# buck_converters_v1_1.net
KiCad netlist of a schematic drawn in EAGLE
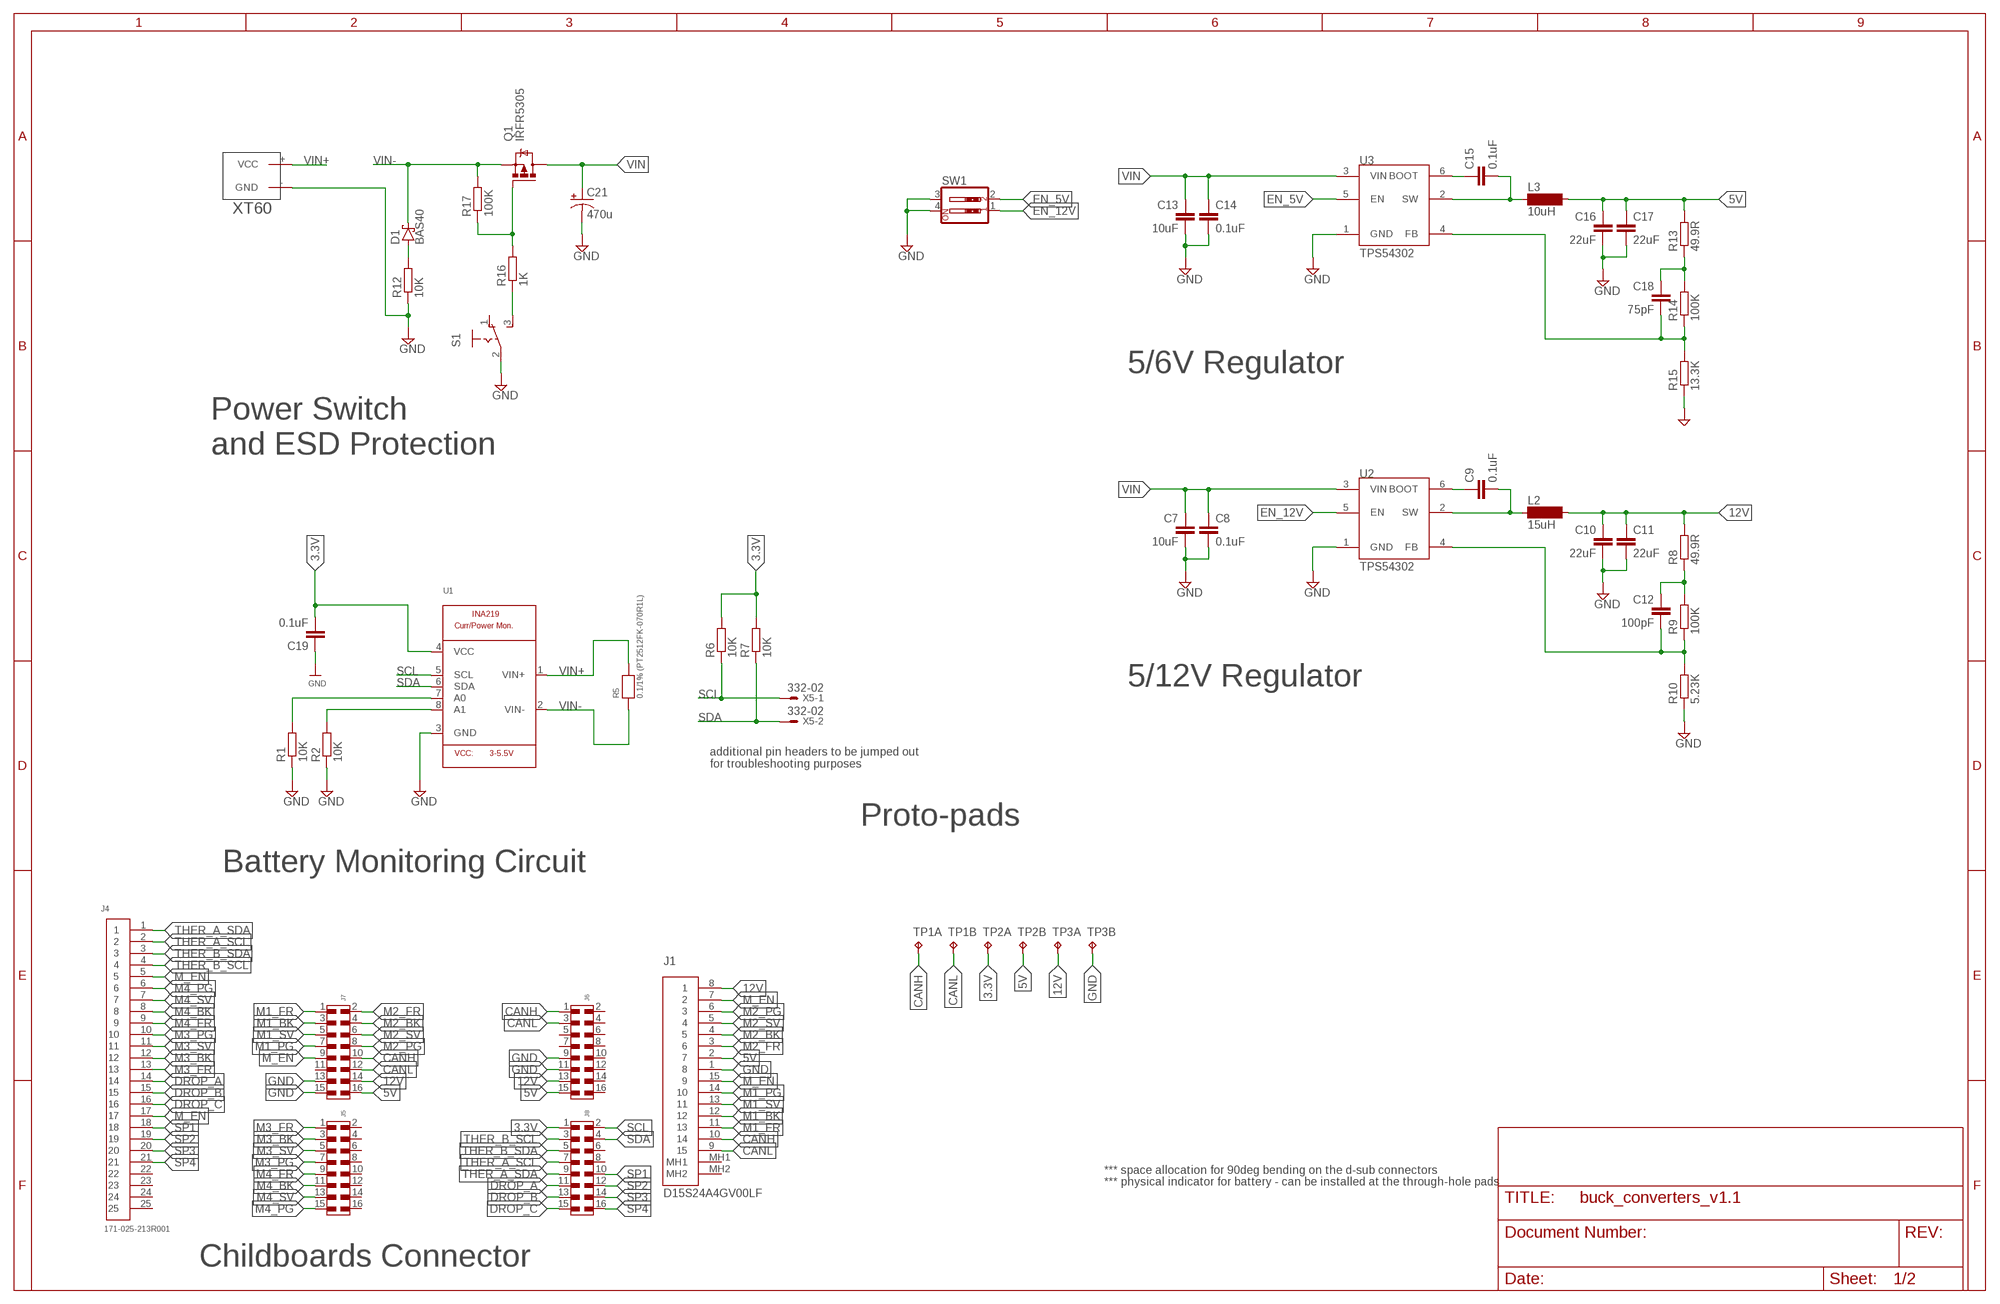
[diagram p0: schematic, sheet 1]
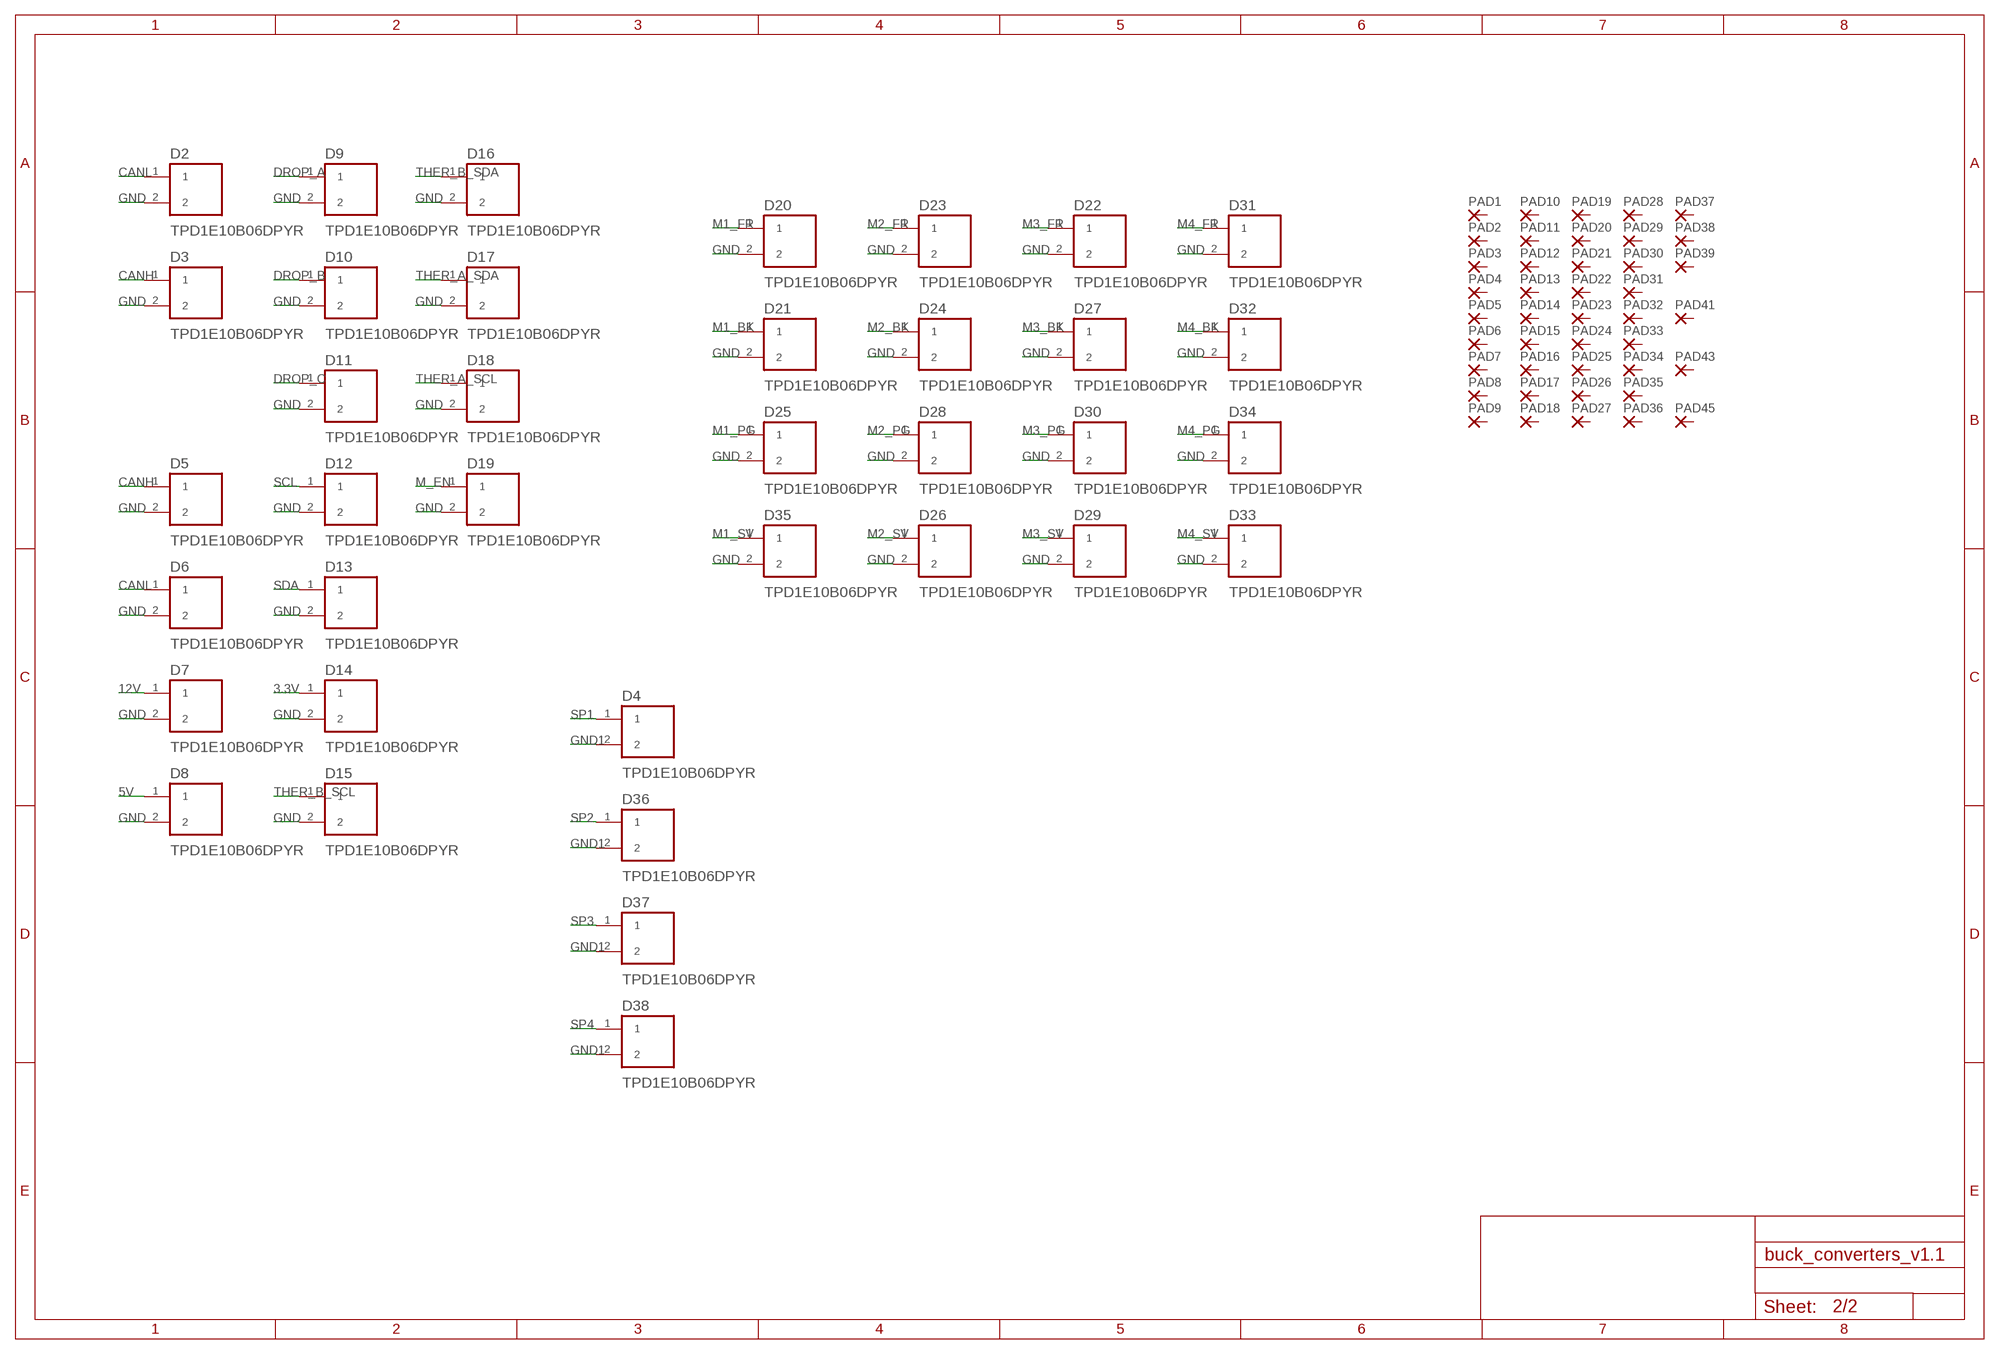
[diagram p1: schematic, sheet 2]

(export (version "E")
  (design (tool "Eeschema 10.0.6"))
  (components
    (comp (ref "D2")
      (value "TPD1E10B06DPYR")
      (footprint "eagle-import:DIO_TPD1E05U06DPYR")
      (fields (field (name "MF") "Texas Instruments"))
      (libsource (lib "eagle-import") (part "TPD1E10B06DPYR"))
    )
    (comp (ref "D3")
      (value "TPD1E10B06DPYR")
      (footprint "eagle-import:DIO_TPD1E05U06DPYR")
      (fields (field (name "MF") "Texas Instruments"))
      (libsource (lib "eagle-import") (part "TPD1E10B06DPYR"))
    )
    (comp (ref "D4")
      (value "TPD1E10B06DPYR")
      (footprint "eagle-import:DIO_TPD1E05U06DPYR")
      (fields (field (name "MF") "Texas Instruments"))
      (libsource (lib "eagle-import") (part "TPD1E10B06DPYR"))
    )
    (comp (ref "D5")
      (value "TPD1E10B06DPYR")
      (footprint "eagle-import:DIO_TPD1E05U06DPYR")
      (fields (field (name "MF") "Texas Instruments"))
      (libsource (lib "eagle-import") (part "TPD1E10B06DPYR"))
    )
    (comp (ref "D6")
      (value "TPD1E10B06DPYR")
      (footprint "eagle-import:DIO_TPD1E05U06DPYR")
      (fields (field (name "MF") "Texas Instruments"))
      (libsource (lib "eagle-import") (part "TPD1E10B06DPYR"))
    )
    (comp (ref "D7")
      (value "TPD1E10B06DPYR")
      (footprint "eagle-import:DIO_TPD1E05U06DPYR")
      (fields (field (name "MF") "Texas Instruments"))
      (libsource (lib "eagle-import") (part "TPD1E10B06DPYR"))
    )
    (comp (ref "D8")
      (value "TPD1E10B06DPYR")
      (footprint "eagle-import:DIO_TPD1E05U06DPYR")
      (fields (field (name "MF") "Texas Instruments"))
      (libsource (lib "eagle-import") (part "TPD1E10B06DPYR"))
    )
    (comp (ref "D9")
      (value "TPD1E10B06DPYR")
      (footprint "eagle-import:DIO_TPD1E05U06DPYR")
      (fields (field (name "MF") "Texas Instruments"))
      (libsource (lib "eagle-import") (part "TPD1E10B06DPYR"))
    )
    (comp (ref "D10")
      (value "TPD1E10B06DPYR")
      (footprint "eagle-import:DIO_TPD1E05U06DPYR")
      (fields (field (name "MF") "Texas Instruments"))
      (libsource (lib "eagle-import") (part "TPD1E10B06DPYR"))
    )
    (comp (ref "D11")
      (value "TPD1E10B06DPYR")
      (footprint "eagle-import:DIO_TPD1E05U06DPYR")
      (fields (field (name "MF") "Texas Instruments"))
      (libsource (lib "eagle-import") (part "TPD1E10B06DPYR"))
    )
    (comp (ref "D12")
      (value "TPD1E10B06DPYR")
      (footprint "eagle-import:DIO_TPD1E05U06DPYR")
      (fields (field (name "MF") "Texas Instruments"))
      (libsource (lib "eagle-import") (part "TPD1E10B06DPYR"))
    )
    (comp (ref "D13")
      (value "TPD1E10B06DPYR")
      (footprint "eagle-import:DIO_TPD1E05U06DPYR")
      (fields (field (name "MF") "Texas Instruments"))
      (libsource (lib "eagle-import") (part "TPD1E10B06DPYR"))
    )
    (comp (ref "D14")
      (value "TPD1E10B06DPYR")
      (footprint "eagle-import:DIO_TPD1E05U06DPYR")
      (fields (field (name "MF") "Texas Instruments"))
      (libsource (lib "eagle-import") (part "TPD1E10B06DPYR"))
    )
    (comp (ref "D15")
      (value "TPD1E10B06DPYR")
      (footprint "eagle-import:DIO_TPD1E05U06DPYR")
      (fields (field (name "MF") "Texas Instruments"))
      (libsource (lib "eagle-import") (part "TPD1E10B06DPYR"))
    )
    (comp (ref "D16")
      (value "TPD1E10B06DPYR")
      (footprint "eagle-import:DIO_TPD1E05U06DPYR")
      (fields (field (name "MF") "Texas Instruments"))
      (libsource (lib "eagle-import") (part "TPD1E10B06DPYR"))
    )
    (comp (ref "D17")
      (value "TPD1E10B06DPYR")
      (footprint "eagle-import:DIO_TPD1E05U06DPYR")
      (fields (field (name "MF") "Texas Instruments"))
      (libsource (lib "eagle-import") (part "TPD1E10B06DPYR"))
    )
    (comp (ref "D18")
      (value "TPD1E10B06DPYR")
      (footprint "eagle-import:DIO_TPD1E05U06DPYR")
      (fields (field (name "MF") "Texas Instruments"))
      (libsource (lib "eagle-import") (part "TPD1E10B06DPYR"))
    )
    (comp (ref "D19")
      (value "TPD1E10B06DPYR")
      (footprint "eagle-import:DIO_TPD1E05U06DPYR")
      (fields (field (name "MF") "Texas Instruments"))
      (libsource (lib "eagle-import") (part "TPD1E10B06DPYR"))
    )
    (comp (ref "D20")
      (value "TPD1E10B06DPYR")
      (footprint "eagle-import:DIO_TPD1E05U06DPYR")
      (fields (field (name "MF") "Texas Instruments"))
      (libsource (lib "eagle-import") (part "TPD1E10B06DPYR"))
    )
    (comp (ref "D21")
      (value "TPD1E10B06DPYR")
      (footprint "eagle-import:DIO_TPD1E05U06DPYR")
      (fields (field (name "MF") "Texas Instruments"))
      (libsource (lib "eagle-import") (part "TPD1E10B06DPYR"))
    )
    (comp (ref "D22")
      (value "TPD1E10B06DPYR")
      (footprint "eagle-import:DIO_TPD1E05U06DPYR")
      (fields (field (name "MF") "Texas Instruments"))
      (libsource (lib "eagle-import") (part "TPD1E10B06DPYR"))
    )
    (comp (ref "D23")
      (value "TPD1E10B06DPYR")
      (footprint "eagle-import:DIO_TPD1E05U06DPYR")
      (fields (field (name "MF") "Texas Instruments"))
      (libsource (lib "eagle-import") (part "TPD1E10B06DPYR"))
    )
    (comp (ref "D24")
      (value "TPD1E10B06DPYR")
      (footprint "eagle-import:DIO_TPD1E05U06DPYR")
      (fields (field (name "MF") "Texas Instruments"))
      (libsource (lib "eagle-import") (part "TPD1E10B06DPYR"))
    )
    (comp (ref "D25")
      (value "TPD1E10B06DPYR")
      (footprint "eagle-import:DIO_TPD1E05U06DPYR")
      (fields (field (name "MF") "Texas Instruments"))
      (libsource (lib "eagle-import") (part "TPD1E10B06DPYR"))
    )
    (comp (ref "D26")
      (value "TPD1E10B06DPYR")
      (footprint "eagle-import:DIO_TPD1E05U06DPYR")
      (fields (field (name "MF") "Texas Instruments"))
      (libsource (lib "eagle-import") (part "TPD1E10B06DPYR"))
    )
    (comp (ref "D27")
      (value "TPD1E10B06DPYR")
      (footprint "eagle-import:DIO_TPD1E05U06DPYR")
      (fields (field (name "MF") "Texas Instruments"))
      (libsource (lib "eagle-import") (part "TPD1E10B06DPYR"))
    )
    (comp (ref "D28")
      (value "TPD1E10B06DPYR")
      (footprint "eagle-import:DIO_TPD1E05U06DPYR")
      (fields (field (name "MF") "Texas Instruments"))
      (libsource (lib "eagle-import") (part "TPD1E10B06DPYR"))
    )
    (comp (ref "D29")
      (value "TPD1E10B06DPYR")
      (footprint "eagle-import:DIO_TPD1E05U06DPYR")
      (fields (field (name "MF") "Texas Instruments"))
      (libsource (lib "eagle-import") (part "TPD1E10B06DPYR"))
    )
    (comp (ref "D30")
      (value "TPD1E10B06DPYR")
      (footprint "eagle-import:DIO_TPD1E05U06DPYR")
      (fields (field (name "MF") "Texas Instruments"))
      (libsource (lib "eagle-import") (part "TPD1E10B06DPYR"))
    )
    (comp (ref "D31")
      (value "TPD1E10B06DPYR")
      (footprint "eagle-import:DIO_TPD1E05U06DPYR")
      (fields (field (name "MF") "Texas Instruments"))
      (libsource (lib "eagle-import") (part "TPD1E10B06DPYR"))
    )
    (comp (ref "D32")
      (value "TPD1E10B06DPYR")
      (footprint "eagle-import:DIO_TPD1E05U06DPYR")
      (fields (field (name "MF") "Texas Instruments"))
      (libsource (lib "eagle-import") (part "TPD1E10B06DPYR"))
    )
    (comp (ref "D33")
      (value "TPD1E10B06DPYR")
      (footprint "eagle-import:DIO_TPD1E05U06DPYR")
      (fields (field (name "MF") "Texas Instruments"))
      (libsource (lib "eagle-import") (part "TPD1E10B06DPYR"))
    )
    (comp (ref "D34")
      (value "TPD1E10B06DPYR")
      (footprint "eagle-import:DIO_TPD1E05U06DPYR")
      (fields (field (name "MF") "Texas Instruments"))
      (libsource (lib "eagle-import") (part "TPD1E10B06DPYR"))
    )
    (comp (ref "D35")
      (value "TPD1E10B06DPYR")
      (footprint "eagle-import:DIO_TPD1E05U06DPYR")
      (fields (field (name "MF") "Texas Instruments"))
      (libsource (lib "eagle-import") (part "TPD1E10B06DPYR"))
    )
    (comp (ref "D36")
      (value "TPD1E10B06DPYR")
      (footprint "eagle-import:DIO_TPD1E05U06DPYR")
      (fields (field (name "MF") "Texas Instruments"))
      (libsource (lib "eagle-import") (part "TPD1E10B06DPYR"))
    )
    (comp (ref "D37")
      (value "TPD1E10B06DPYR")
      (footprint "eagle-import:DIO_TPD1E05U06DPYR")
      (fields (field (name "MF") "Texas Instruments"))
      (libsource (lib "eagle-import") (part "TPD1E10B06DPYR"))
    )
    (comp (ref "D38")
      (value "TPD1E10B06DPYR")
      (footprint "eagle-import:DIO_TPD1E05U06DPYR")
      (fields (field (name "MF") "Texas Instruments"))
      (libsource (lib "eagle-import") (part "TPD1E10B06DPYR"))
    )
    (comp (ref "PAD1")
      (value "2,54/1,1")
      (footprint "eagle-import:2,54_1,1")
      (libsource (lib "eagle-import") (part "2,54/1,1"))
    )
    (comp (ref "PAD2")
      (value "2,54/1,1")
      (footprint "eagle-import:2,54_1,1")
      (libsource (lib "eagle-import") (part "2,54/1,1"))
    )
    (comp (ref "PAD3")
      (value "2,54/1,1")
      (footprint "eagle-import:2,54_1,1")
      (libsource (lib "eagle-import") (part "2,54/1,1"))
    )
    (comp (ref "PAD4")
      (value "2,54/1,1")
      (footprint "eagle-import:2,54_1,1")
      (libsource (lib "eagle-import") (part "2,54/1,1"))
    )
    (comp (ref "PAD5")
      (value "2,54/1,1")
      (footprint "eagle-import:2,54_1,1")
      (libsource (lib "eagle-import") (part "2,54/1,1"))
    )
    (comp (ref "PAD6")
      (value "2,54/1,1")
      (footprint "eagle-import:2,54_1,1")
      (libsource (lib "eagle-import") (part "2,54/1,1"))
    )
    (comp (ref "PAD7")
      (value "2,54/1,1")
      (footprint "eagle-import:2,54_1,1")
      (libsource (lib "eagle-import") (part "2,54/1,1"))
    )
    (comp (ref "PAD8")
      (value "2,54/1,1")
      (footprint "eagle-import:2,54_1,1")
      (libsource (lib "eagle-import") (part "2,54/1,1"))
    )
    (comp (ref "PAD9")
      (value "2,54/1,1")
      (footprint "eagle-import:2,54_1,1")
      (libsource (lib "eagle-import") (part "2,54/1,1"))
    )
    (comp (ref "PAD10")
      (value "2,54/1,1")
      (footprint "eagle-import:2,54_1,1")
      (libsource (lib "eagle-import") (part "2,54/1,1"))
    )
    (comp (ref "PAD11")
      (value "2,54/1,1")
      (footprint "eagle-import:2,54_1,1")
      (libsource (lib "eagle-import") (part "2,54/1,1"))
    )
    (comp (ref "PAD12")
      (value "2,54/1,1")
      (footprint "eagle-import:2,54_1,1")
      (libsource (lib "eagle-import") (part "2,54/1,1"))
    )
    (comp (ref "PAD13")
      (value "2,54/1,1")
      (footprint "eagle-import:2,54_1,1")
      (libsource (lib "eagle-import") (part "2,54/1,1"))
    )
    (comp (ref "PAD14")
      (value "2,54/1,1")
      (footprint "eagle-import:2,54_1,1")
      (libsource (lib "eagle-import") (part "2,54/1,1"))
    )
    (comp (ref "PAD15")
      (value "2,54/1,1")
      (footprint "eagle-import:2,54_1,1")
      (libsource (lib "eagle-import") (part "2,54/1,1"))
    )
    (comp (ref "PAD16")
      (value "2,54/1,1")
      (footprint "eagle-import:2,54_1,1")
      (libsource (lib "eagle-import") (part "2,54/1,1"))
    )
    (comp (ref "PAD17")
      (value "2,54/1,1")
      (footprint "eagle-import:2,54_1,1")
      (libsource (lib "eagle-import") (part "2,54/1,1"))
    )
    (comp (ref "PAD18")
      (value "2,54/1,1")
      (footprint "eagle-import:2,54_1,1")
      (libsource (lib "eagle-import") (part "2,54/1,1"))
    )
    (comp (ref "PAD19")
      (value "2,54/1,1")
      (footprint "eagle-import:2,54_1,1")
      (libsource (lib "eagle-import") (part "2,54/1,1"))
    )
    (comp (ref "PAD20")
      (value "2,54/1,1")
      (footprint "eagle-import:2,54_1,1")
      (libsource (lib "eagle-import") (part "2,54/1,1"))
    )
    (comp (ref "PAD21")
      (value "2,54/1,1")
      (footprint "eagle-import:2,54_1,1")
      (libsource (lib "eagle-import") (part "2,54/1,1"))
    )
    (comp (ref "PAD22")
      (value "2,54/1,1")
      (footprint "eagle-import:2,54_1,1")
      (libsource (lib "eagle-import") (part "2,54/1,1"))
    )
    (comp (ref "PAD23")
      (value "2,54/1,1")
      (footprint "eagle-import:2,54_1,1")
      (libsource (lib "eagle-import") (part "2,54/1,1"))
    )
    (comp (ref "PAD24")
      (value "2,54/1,1")
      (footprint "eagle-import:2,54_1,1")
      (libsource (lib "eagle-import") (part "2,54/1,1"))
    )
    (comp (ref "PAD25")
      (value "2,54/1,1")
      (footprint "eagle-import:2,54_1,1")
      (libsource (lib "eagle-import") (part "2,54/1,1"))
    )
    (comp (ref "PAD26")
      (value "2,54/1,1")
      (footprint "eagle-import:2,54_1,1")
      (libsource (lib "eagle-import") (part "2,54/1,1"))
    )
    (comp (ref "PAD27")
      (value "2,54/1,1")
      (footprint "eagle-import:2,54_1,1")
      (libsource (lib "eagle-import") (part "2,54/1,1"))
    )
    (comp (ref "PAD28")
      (value "2,54/1,1")
      (footprint "eagle-import:2,54_1,1")
      (libsource (lib "eagle-import") (part "2,54/1,1"))
    )
    (comp (ref "PAD29")
      (value "2,54/1,1")
      (footprint "eagle-import:2,54_1,1")
      (libsource (lib "eagle-import") (part "2,54/1,1"))
    )
    (comp (ref "PAD30")
      (value "2,54/1,1")
      (footprint "eagle-import:2,54_1,1")
      (libsource (lib "eagle-import") (part "2,54/1,1"))
    )
    (comp (ref "PAD31")
      (value "2,54/1,1")
      (footprint "eagle-import:2,54_1,1")
      (libsource (lib "eagle-import") (part "2,54/1,1"))
    )
    (comp (ref "PAD32")
      (value "2,54/1,1")
      (footprint "eagle-import:2,54_1,1")
      (libsource (lib "eagle-import") (part "2,54/1,1"))
    )
    (comp (ref "PAD33")
      (value "2,54/1,1")
      (footprint "eagle-import:2,54_1,1")
      (libsource (lib "eagle-import") (part "2,54/1,1"))
    )
    (comp (ref "PAD34")
      (value "2,54/1,1")
      (footprint "eagle-import:2,54_1,1")
      (libsource (lib "eagle-import") (part "2,54/1,1"))
    )
    (comp (ref "PAD35")
      (value "2,54/1,1")
      (footprint "eagle-import:2,54_1,1")
      (libsource (lib "eagle-import") (part "2,54/1,1"))
    )
    (comp (ref "PAD36")
      (value "2,54/1,1")
      (footprint "eagle-import:2,54_1,1")
      (libsource (lib "eagle-import") (part "2,54/1,1"))
    )
    (comp (ref "PAD37")
      (value "2,54/1,1")
      (footprint "eagle-import:2,54_1,1")
      (libsource (lib "eagle-import") (part "2,54/1,1"))
    )
    (comp (ref "PAD38")
      (value "2,54/1,1")
      (footprint "eagle-import:2,54_1,1")
      (libsource (lib "eagle-import") (part "2,54/1,1"))
    )
    (comp (ref "PAD39")
      (value "2,54/1,1")
      (footprint "eagle-import:2,54_1,1")
      (libsource (lib "eagle-import") (part "2,54/1,1"))
    )
    (comp (ref "PAD41")
      (value "2,54/1,1")
      (footprint "eagle-import:2,54_1,1")
      (libsource (lib "eagle-import") (part "2,54/1,1"))
    )
    (comp (ref "PAD43")
      (value "2,54/1,1")
      (footprint "eagle-import:2,54_1,1")
      (libsource (lib "eagle-import") (part "2,54/1,1"))
    )
    (comp (ref "PAD45")
      (value "2,54/1,1")
      (footprint "eagle-import:2,54_1,1")
      (libsource (lib "eagle-import") (part "2,54/1,1"))
    )
    (comp (ref "C7")
      (value "10uF")
      (footprint "eagle-import:C0805")
      (libsource (lib "eagle-import") (part "C-EUC0805"))
    )
    (comp (ref "C8")
      (value "0.1uF")
      (footprint "eagle-import:C0805")
      (libsource (lib "eagle-import") (part "C-EUC0805"))
    )
    (comp (ref "C9")
      (value "0.1uF")
      (footprint "eagle-import:C0805")
      (libsource (lib "eagle-import") (part "C-EUC0805"))
    )
    (comp (ref "C10")
      (value "22uF")
      (footprint "eagle-import:C0805")
      (libsource (lib "eagle-import") (part "C-EUC0805"))
    )
    (comp (ref "C11")
      (value "22uF")
      (footprint "eagle-import:C0805")
      (libsource (lib "eagle-import") (part "C-EUC0805"))
    )
    (comp (ref "C12")
      (value "100pF")
      (footprint "eagle-import:C0805")
      (libsource (lib "eagle-import") (part "C-EUC0805"))
    )
    (comp (ref "C13")
      (value "10uF")
      (footprint "eagle-import:C0805")
      (libsource (lib "eagle-import") (part "C-EUC0805"))
    )
    (comp (ref "C14")
      (value "0.1uF")
      (footprint "eagle-import:C0805")
      (libsource (lib "eagle-import") (part "C-EUC0805"))
    )
    (comp (ref "C15")
      (value "0.1uF")
      (footprint "eagle-import:C0805")
      (libsource (lib "eagle-import") (part "C-EUC0805"))
    )
    (comp (ref "C16")
      (value "22uF")
      (footprint "eagle-import:C0805")
      (libsource (lib "eagle-import") (part "C-EUC0805"))
    )
    (comp (ref "C17")
      (value "22uF")
      (footprint "eagle-import:C0805")
      (libsource (lib "eagle-import") (part "C-EUC0805"))
    )
    (comp (ref "C18")
      (value "75pF")
      (footprint "eagle-import:C0805")
      (libsource (lib "eagle-import") (part "C-EUC0805"))
    )
    (comp (ref "C19")
      (value "0.1uF")
      (footprint "eagle-import:C0805")
      (libsource (lib "eagle-import") (part "C-EUC0805"))
    )
    (comp (ref "C21")
      (value "470u")
      (footprint "eagle-import:153CLV-1010")
      (libsource (lib "eagle-import") (part "CPOL-US153CLV-1010"))
    )
    (comp (ref "D1")
      (value "BAS40")
      (footprint "eagle-import:SOT23")
      (libsource (lib "eagle-import") (part "BAS40"))
    )
    (comp (ref "J1")
      (value "D15S24A4GV00LF")
      (footprint "eagle-import:D15S24A4GV00LF")
      (fields
        (field (name "DIGIKEY_PART_NUMBER") "609-1497-ND")
        (field (name "MANUFACTURER") "Amphenol ICC (FCI)")
        (field (name "CREATED_BY") "PCBLayout.com")
      )
      (libsource (lib "eagle-import") (part "D15S24A4GV00LF"))
    )
    (comp (ref "J4")
      (value "171-025-213R001")
      (footprint "eagle-import:171-025-213R001")
      (fields
        (field (name "DIGIKEY_PART_NO") "4225FE-ND")
        (field (name "MANUFACTURER") "NorComp Inc.")
        (field (name "CREATED_BY") "PCBLayout.com")
      )
      (libsource (lib "eagle-import") (part "171-025-213R001"))
    )
    (comp (ref "J5")
      (value "6120XX20621_61201620621")
      (footprint "eagle-import:61201620621")
      (libsource (lib "eagle-import") (part "6120XX20621_61201620621"))
    )
    (comp (ref "J6")
      (value "6120XX20621_61201620621")
      (footprint "eagle-import:61201620621")
      (libsource (lib "eagle-import") (part "6120XX20621_61201620621"))
    )
    (comp (ref "J7")
      (value "6123XX20621_61231620621")
      (footprint "eagle-import:61231620621")
      (libsource (lib "eagle-import") (part "6123XX20621_61231620621"))
    )
    (comp (ref "J8")
      (value "6120XX20621_61201620621")
      (footprint "eagle-import:61201620621")
      (libsource (lib "eagle-import") (part "6120XX20621_61201620621"))
    )
    (comp (ref "L2")
      (value "15uH")
      (footprint "eagle-import:SM-NE29")
      (libsource (lib "eagle-import") (part "SM-NE29"))
    )
    (comp (ref "L3")
      (value "10uH")
      (footprint "eagle-import:SM-NE29")
      (libsource (lib "eagle-import") (part "SM-NE29"))
    )
    (comp (ref "Q1")
      (value "IRFR5305")
      (footprint "eagle-import:D-PAK_TO252AA")
      (libsource (lib "eagle-import") (part "IRF?5305R"))
    )
    (comp (ref "R1")
      (value "10K")
      (footprint "eagle-import:R0805")
      (libsource (lib "eagle-import") (part "R-EU_R0805"))
    )
    (comp (ref "R2")
      (value "10K")
      (footprint "eagle-import:R0805")
      (libsource (lib "eagle-import") (part "R-EU_R0805"))
    )
    (comp (ref "R5")
      (value "0.1/1% (PT2512FK-070R1L)")
      (footprint "eagle-import:2512")
      (libsource (lib "eagle-import") (part "RESISTOR2512"))
    )
    (comp (ref "R6")
      (value "10K")
      (footprint "eagle-import:R0805")
      (libsource (lib "eagle-import") (part "R-EU_R0805"))
    )
    (comp (ref "R7")
      (value "10K")
      (footprint "eagle-import:R0805")
      (libsource (lib "eagle-import") (part "R-EU_R0805"))
    )
    (comp (ref "R8")
      (value "49.9R")
      (footprint "eagle-import:R0805")
      (libsource (lib "eagle-import") (part "R-EU_R0805"))
    )
    (comp (ref "R9")
      (value "100K")
      (footprint "eagle-import:R0805")
      (libsource (lib "eagle-import") (part "R-EU_R0805"))
    )
    (comp (ref "R10")
      (value "5.23K")
      (footprint "eagle-import:R0805")
      (libsource (lib "eagle-import") (part "R-EU_R0805"))
    )
    (comp (ref "R12")
      (value "10K")
      (footprint "eagle-import:R0805")
      (libsource (lib "eagle-import") (part "R-EU_R0805"))
    )
    (comp (ref "R13")
      (value "49.9R")
      (footprint "eagle-import:R0805")
      (libsource (lib "eagle-import") (part "R-EU_R0805"))
    )
    (comp (ref "R14")
      (value "100K")
      (footprint "eagle-import:R0805")
      (libsource (lib "eagle-import") (part "R-EU_R0805"))
    )
    (comp (ref "R15")
      (value "13.3K")
      (footprint "eagle-import:R0805")
      (libsource (lib "eagle-import") (part "R-EU_R0805"))
    )
    (comp (ref "R16")
      (value "1K")
      (footprint "eagle-import:R0805")
      (libsource (lib "eagle-import") (part "R-EU_R0805"))
    )
    (comp (ref "R17")
      (value "100K")
      (footprint "eagle-import:R0805")
      (libsource (lib "eagle-import") (part "R-EU_R0805"))
    )
    (comp (ref "S1")
      (value "255SB")
      (footprint "eagle-import:255SB")
      (libsource (lib "eagle-import") (part "255SB"))
    )
    (comp (ref "SW1")
      (value "SW_DIP-2")
      (footprint "eagle-import:EDG-02")
      (libsource (lib "eagle-import") (part "SW_DIP-2"))
    )
    (comp (ref "TP1")
      (value "TP2P2-38-17")
      (footprint "eagle-import:P2-38-17")
      (libsource (lib "eagle-import") (part "TP2P2-38-17"))
    )
    (comp (ref "TP2")
      (value "TP2P2-38-17")
      (footprint "eagle-import:P2-38-17")
      (libsource (lib "eagle-import") (part "TP2P2-38-17"))
    )
    (comp (ref "TP3")
      (value "TP2P2-38-17")
      (footprint "eagle-import:P2-38-17")
      (libsource (lib "eagle-import") (part "TP2P2-38-17"))
    )
    (comp (ref "U$9")
      (value "XT60")
      (footprint "eagle-import:XT60")
      (libsource (lib "eagle-import") (part "XT60"))
    )
    (comp (ref "U1")
      (value "INA219")
      (footprint "eagle-import:SOT23-8")
      (libsource (lib "eagle-import") (part "INA219"))
    )
    (comp (ref "U2")
      (value "TPS54302")
      (footprint "eagle-import:SOT23-6")
      (libsource (lib "eagle-import") (part "TPS54302"))
    )
    (comp (ref "U3")
      (value "TPS54302")
      (footprint "eagle-import:SOT23-6")
      (libsource (lib "eagle-import") (part "TPS54302"))
    )
    (comp (ref "X5")
      (value "332-02")
      (footprint "eagle-import:332-02")
      (libsource (lib "eagle-import") (part "332-02"))
    )
  )
  (nets
    (net (code "1") (name "3.3V") (class "Default")
      (node (ref "C19") (pin "2") (pinfunction "2_2") (pintype "passive"))
      (node (ref "D14") (pin "1") (pinfunction "1_1") (pintype "bidirectional"))
      (node (ref "J8") (pin "1") (pinfunction "1_1") (pintype "passive"))
      (node (ref "R6") (pin "2") (pinfunction "2_2") (pintype "passive"))
      (node (ref "R7") (pin "2") (pinfunction "2_2") (pintype "passive"))
      (node (ref "TP2") (pin "TP-1") (pinfunction "TP_TP-1") (pintype "input"))
      (node (ref "U1") (pin "4") (pinfunction "VCC_4") (pintype "bidirectional"))
    )
    (net (code "2") (name "5V") (class "Default")
      (node (ref "C16") (pin "1") (pinfunction "1_1") (pintype "passive"))
      (node (ref "C17") (pin "1") (pinfunction "1_1") (pintype "passive"))
      (node (ref "D8") (pin "1") (pinfunction "1_1") (pintype "bidirectional"))
      (node (ref "J1") (pin "2") (pinfunction "7_2") (pintype "passive"))
      (node (ref "J6") (pin "15") (pinfunction "15_15") (pintype "passive"))
      (node (ref "J7") (pin "16") (pinfunction "16_16") (pintype "passive"))
      (node (ref "L3") (pin "2") (pinfunction "2_2") (pintype "passive"))
      (node (ref "R13") (pin "2") (pinfunction "2_2") (pintype "passive"))
      (node (ref "TP2") (pin "TP-2") (pinfunction "TP_TP-2") (pintype "input"))
    )
    (net (code "3") (name "12V") (class "Default")
      (node (ref "C10") (pin "1") (pinfunction "1_1") (pintype "passive"))
      (node (ref "C11") (pin "1") (pinfunction "1_1") (pintype "passive"))
      (node (ref "D7") (pin "1") (pinfunction "1_1") (pintype "bidirectional"))
      (node (ref "J1") (pin "8") (pinfunction "1_8") (pintype "passive"))
      (node (ref "J6") (pin "13") (pinfunction "13_13") (pintype "passive"))
      (node (ref "J7") (pin "14") (pinfunction "14_14") (pintype "passive"))
      (node (ref "L2") (pin "2") (pinfunction "2_2") (pintype "passive"))
      (node (ref "R8") (pin "2") (pinfunction "2_2") (pintype "passive"))
      (node (ref "TP3") (pin "TP-1") (pinfunction "TP_TP-1") (pintype "input"))
    )
    (net (code "4") (name "CANH") (class "Default")
      (node (ref "D3") (pin "1") (pinfunction "1_1") (pintype "bidirectional"))
      (node (ref "D5") (pin "1") (pinfunction "1_1") (pintype "bidirectional"))
      (node (ref "J1") (pin "10") (pinfunction "14_10") (pintype "passive"))
      (node (ref "J6") (pin "1") (pinfunction "1_1") (pintype "passive"))
      (node (ref "J7") (pin "10") (pinfunction "10_10") (pintype "passive"))
      (node (ref "TP1") (pin "TP-1") (pinfunction "TP_TP-1") (pintype "input"))
    )
    (net (code "5") (name "CANL") (class "Default")
      (node (ref "D2") (pin "1") (pinfunction "1_1") (pintype "bidirectional"))
      (node (ref "D6") (pin "1") (pinfunction "1_1") (pintype "bidirectional"))
      (node (ref "J1") (pin "9") (pinfunction "15_9") (pintype "passive"))
      (node (ref "J6") (pin "3") (pinfunction "3_3") (pintype "passive"))
      (node (ref "J7") (pin "12") (pinfunction "12_12") (pintype "passive"))
      (node (ref "TP1") (pin "TP-2") (pinfunction "TP_TP-2") (pintype "input"))
    )
    (net (code "6") (name "DROP_A") (class "Default")
      (node (ref "D9") (pin "1") (pinfunction "1_1") (pintype "bidirectional"))
      (node (ref "J4") (pin "14") (pinfunction "14_14") (pintype "passive"))
      (node (ref "J8") (pin "11") (pinfunction "11_11") (pintype "passive"))
    )
    (net (code "7") (name "DROP_B") (class "Default")
      (node (ref "D10") (pin "1") (pinfunction "1_1") (pintype "bidirectional"))
      (node (ref "J4") (pin "15") (pinfunction "15_15") (pintype "passive"))
      (node (ref "J8") (pin "13") (pinfunction "13_13") (pintype "passive"))
    )
    (net (code "8") (name "DROP_C") (class "Default")
      (node (ref "D11") (pin "1") (pinfunction "1_1") (pintype "bidirectional"))
      (node (ref "J4") (pin "16") (pinfunction "16_16") (pintype "passive"))
      (node (ref "J8") (pin "15") (pinfunction "15_15") (pintype "passive"))
    )
    (net (code "9") (name "EN_5V") (class "Default")
      (node (ref "SW1") (pin "2") (pinfunction "2_2") (pintype "passive"))
      (node (ref "U3") (pin "5") (pinfunction "EN_5") (pintype "bidirectional"))
    )
    (net (code "10") (name "EN_12V") (class "Default")
      (node (ref "SW1") (pin "1") (pinfunction "1_1") (pintype "passive"))
      (node (ref "U2") (pin "5") (pinfunction "EN_5") (pintype "bidirectional"))
    )
    (net (code "11") (name "GND") (class "Default")
      (node (ref "C10") (pin "2") (pinfunction "2_2") (pintype "passive"))
      (node (ref "C11") (pin "2") (pinfunction "2_2") (pintype "passive"))
      (node (ref "C13") (pin "2") (pinfunction "2_2") (pintype "passive"))
      (node (ref "C14") (pin "2") (pinfunction "2_2") (pintype "passive"))
      (node (ref "C16") (pin "2") (pinfunction "2_2") (pintype "passive"))
      (node (ref "C17") (pin "2") (pinfunction "2_2") (pintype "passive"))
      (node (ref "C19") (pin "1") (pinfunction "1_1") (pintype "passive"))
      (node (ref "C21") (pin "-") (pinfunction "-_-") (pintype "passive"))
      (node (ref "C7") (pin "2") (pinfunction "2_2") (pintype "passive"))
      (node (ref "C8") (pin "2") (pinfunction "2_2") (pintype "passive"))
      (node (ref "D10") (pin "2") (pinfunction "2_2") (pintype "bidirectional"))
      (node (ref "D11") (pin "2") (pinfunction "2_2") (pintype "bidirectional"))
      (node (ref "D12") (pin "2") (pinfunction "2_2") (pintype "bidirectional"))
      (node (ref "D13") (pin "2") (pinfunction "2_2") (pintype "bidirectional"))
      (node (ref "D14") (pin "2") (pinfunction "2_2") (pintype "bidirectional"))
      (node (ref "D15") (pin "2") (pinfunction "2_2") (pintype "bidirectional"))
      (node (ref "D16") (pin "2") (pinfunction "2_2") (pintype "bidirectional"))
      (node (ref "D17") (pin "2") (pinfunction "2_2") (pintype "bidirectional"))
      (node (ref "D18") (pin "2") (pinfunction "2_2") (pintype "bidirectional"))
      (node (ref "D19") (pin "2") (pinfunction "2_2") (pintype "bidirectional"))
      (node (ref "D2") (pin "2") (pinfunction "2_2") (pintype "bidirectional"))
      (node (ref "D20") (pin "2") (pinfunction "2_2") (pintype "bidirectional"))
      (node (ref "D21") (pin "2") (pinfunction "2_2") (pintype "bidirectional"))
      (node (ref "D22") (pin "2") (pinfunction "2_2") (pintype "bidirectional"))
      (node (ref "D23") (pin "2") (pinfunction "2_2") (pintype "bidirectional"))
      (node (ref "D24") (pin "2") (pinfunction "2_2") (pintype "bidirectional"))
      (node (ref "D25") (pin "2") (pinfunction "2_2") (pintype "bidirectional"))
      (node (ref "D26") (pin "2") (pinfunction "2_2") (pintype "bidirectional"))
      (node (ref "D27") (pin "2") (pinfunction "2_2") (pintype "bidirectional"))
      (node (ref "D28") (pin "2") (pinfunction "2_2") (pintype "bidirectional"))
      (node (ref "D29") (pin "2") (pinfunction "2_2") (pintype "bidirectional"))
      (node (ref "D3") (pin "2") (pinfunction "2_2") (pintype "bidirectional"))
      (node (ref "D30") (pin "2") (pinfunction "2_2") (pintype "bidirectional"))
      (node (ref "D31") (pin "2") (pinfunction "2_2") (pintype "bidirectional"))
      (node (ref "D32") (pin "2") (pinfunction "2_2") (pintype "bidirectional"))
      (node (ref "D33") (pin "2") (pinfunction "2_2") (pintype "bidirectional"))
      (node (ref "D34") (pin "2") (pinfunction "2_2") (pintype "bidirectional"))
      (node (ref "D35") (pin "2") (pinfunction "2_2") (pintype "bidirectional"))
      (node (ref "D5") (pin "2") (pinfunction "2_2") (pintype "bidirectional"))
      (node (ref "D6") (pin "2") (pinfunction "2_2") (pintype "bidirectional"))
      (node (ref "D7") (pin "2") (pinfunction "2_2") (pintype "bidirectional"))
      (node (ref "D8") (pin "2") (pinfunction "2_2") (pintype "bidirectional"))
      (node (ref "D9") (pin "2") (pinfunction "2_2") (pintype "bidirectional"))
      (node (ref "J1") (pin "1") (pinfunction "8_1") (pintype "passive"))
      (node (ref "J6") (pin "11") (pinfunction "11_11") (pintype "passive"))
      (node (ref "J6") (pin "9") (pinfunction "9_9") (pintype "passive"))
      (node (ref "J7") (pin "13") (pinfunction "13_13") (pintype "passive"))
      (node (ref "J7") (pin "15") (pinfunction "15_15") (pintype "passive"))
      (node (ref "R1") (pin "1") (pinfunction "1_1") (pintype "passive"))
      (node (ref "R10") (pin "1") (pinfunction "1_1") (pintype "passive"))
      (node (ref "R12") (pin "1") (pinfunction "1_1") (pintype "passive"))
      (node (ref "R15") (pin "1") (pinfunction "1_1") (pintype "passive"))
      (node (ref "R2") (pin "1") (pinfunction "1_1") (pintype "passive"))
      (node (ref "S1") (pin "2") (pinfunction "P_2") (pintype "passive"))
      (node (ref "SW1") (pin "3") (pinfunction "3_3") (pintype "passive"))
      (node (ref "SW1") (pin "4") (pinfunction "4_4") (pintype "passive"))
      (node (ref "TP3") (pin "TP-2") (pinfunction "TP_TP-2") (pintype "input"))
      (node (ref "U$9") (pin "-") (pinfunction "GND_-") (pintype "bidirectional"))
      (node (ref "U1") (pin "3") (pinfunction "GND_3") (pintype "bidirectional"))
      (node (ref "U2") (pin "1") (pinfunction "GND_1") (pintype "bidirectional"))
      (node (ref "U3") (pin "1") (pinfunction "GND_1") (pintype "bidirectional"))
    )
    (net (code "12") (name "GND1") (class "Default")
      (node (ref "D36") (pin "2") (pinfunction "2_2") (pintype "bidirectional"))
      (node (ref "D37") (pin "2") (pinfunction "2_2") (pintype "bidirectional"))
      (node (ref "D38") (pin "2") (pinfunction "2_2") (pintype "bidirectional"))
      (node (ref "D4") (pin "2") (pinfunction "2_2") (pintype "bidirectional"))
    )
    (net (code "13") (name "M1_BK") (class "Default")
      (node (ref "D21") (pin "1") (pinfunction "1_1") (pintype "bidirectional"))
      (node (ref "J1") (pin "12") (pinfunction "12_12") (pintype "passive"))
      (node (ref "J7") (pin "3") (pinfunction "3_3") (pintype "passive"))
    )
    (net (code "14") (name "M1_FR") (class "Default")
      (node (ref "D20") (pin "1") (pinfunction "1_1") (pintype "bidirectional"))
      (node (ref "J1") (pin "11") (pinfunction "13_11") (pintype "passive"))
      (node (ref "J7") (pin "1") (pinfunction "1_1") (pintype "passive"))
    )
    (net (code "15") (name "M1_PG") (class "Default")
      (node (ref "D25") (pin "1") (pinfunction "1_1") (pintype "bidirectional"))
      (node (ref "J1") (pin "14") (pinfunction "10_14") (pintype "passive"))
      (node (ref "J7") (pin "7") (pinfunction "7_7") (pintype "passive"))
    )
    (net (code "16") (name "M1_SV") (class "Default")
      (node (ref "D35") (pin "1") (pinfunction "1_1") (pintype "bidirectional"))
      (node (ref "J1") (pin "13") (pinfunction "11_13") (pintype "passive"))
      (node (ref "J7") (pin "5") (pinfunction "5_5") (pintype "passive"))
    )
    (net (code "17") (name "M2_BK") (class "Default")
      (node (ref "D24") (pin "1") (pinfunction "1_1") (pintype "bidirectional"))
      (node (ref "J1") (pin "4") (pinfunction "5_4") (pintype "passive"))
      (node (ref "J7") (pin "4") (pinfunction "4_4") (pintype "passive"))
    )
    (net (code "18") (name "M2_FR") (class "Default")
      (node (ref "D23") (pin "1") (pinfunction "1_1") (pintype "bidirectional"))
      (node (ref "J1") (pin "3") (pinfunction "6_3") (pintype "passive"))
      (node (ref "J7") (pin "2") (pinfunction "2_2") (pintype "passive"))
    )
    (net (code "19") (name "M2_PG") (class "Default")
      (node (ref "D28") (pin "1") (pinfunction "1_1") (pintype "bidirectional"))
      (node (ref "J1") (pin "6") (pinfunction "3_6") (pintype "passive"))
      (node (ref "J7") (pin "8") (pinfunction "8_8") (pintype "passive"))
    )
    (net (code "20") (name "M2_SV") (class "Default")
      (node (ref "D26") (pin "1") (pinfunction "1_1") (pintype "bidirectional"))
      (node (ref "J1") (pin "5") (pinfunction "4_5") (pintype "passive"))
      (node (ref "J7") (pin "6") (pinfunction "6_6") (pintype "passive"))
    )
    (net (code "21") (name "M3_BK") (class "Default")
      (node (ref "D27") (pin "1") (pinfunction "1_1") (pintype "bidirectional"))
      (node (ref "J4") (pin "12") (pinfunction "12_12") (pintype "passive"))
      (node (ref "J5") (pin "3") (pinfunction "3_3") (pintype "passive"))
    )
    (net (code "22") (name "M3_FR") (class "Default")
      (node (ref "D22") (pin "1") (pinfunction "1_1") (pintype "bidirectional"))
      (node (ref "J4") (pin "13") (pinfunction "13_13") (pintype "passive"))
      (node (ref "J5") (pin "1") (pinfunction "1_1") (pintype "passive"))
    )
    (net (code "23") (name "M3_PG") (class "Default")
      (node (ref "D30") (pin "1") (pinfunction "1_1") (pintype "bidirectional"))
      (node (ref "J4") (pin "10") (pinfunction "10_10") (pintype "passive"))
      (node (ref "J5") (pin "7") (pinfunction "7_7") (pintype "passive"))
    )
    (net (code "24") (name "M3_SV") (class "Default")
      (node (ref "D29") (pin "1") (pinfunction "1_1") (pintype "bidirectional"))
      (node (ref "J4") (pin "11") (pinfunction "11_11") (pintype "passive"))
      (node (ref "J5") (pin "5") (pinfunction "5_5") (pintype "passive"))
    )
    (net (code "25") (name "M4_BK") (class "Default")
      (node (ref "D32") (pin "1") (pinfunction "1_1") (pintype "bidirectional"))
      (node (ref "J4") (pin "8") (pinfunction "8_8") (pintype "passive"))
      (node (ref "J5") (pin "11") (pinfunction "11_11") (pintype "passive"))
    )
    (net (code "26") (name "M4_FR") (class "Default")
      (node (ref "D31") (pin "1") (pinfunction "1_1") (pintype "bidirectional"))
      (node (ref "J4") (pin "9") (pinfunction "9_9") (pintype "passive"))
      (node (ref "J5") (pin "9") (pinfunction "9_9") (pintype "passive"))
    )
    (net (code "27") (name "M4_PG") (class "Default")
      (node (ref "D34") (pin "1") (pinfunction "1_1") (pintype "bidirectional"))
      (node (ref "J4") (pin "6") (pinfunction "6_6") (pintype "passive"))
      (node (ref "J5") (pin "15") (pinfunction "15_15") (pintype "passive"))
    )
    (net (code "28") (name "M4_SV") (class "Default")
      (node (ref "D33") (pin "1") (pinfunction "1_1") (pintype "bidirectional"))
      (node (ref "J4") (pin "7") (pinfunction "7_7") (pintype "passive"))
      (node (ref "J5") (pin "13") (pinfunction "13_13") (pintype "passive"))
    )
    (net (code "29") (name "M_EN") (class "Default")
      (node (ref "D19") (pin "1") (pinfunction "1_1") (pintype "bidirectional"))
      (node (ref "J1") (pin "15") (pinfunction "9_15") (pintype "passive"))
      (node (ref "J1") (pin "7") (pinfunction "2_7") (pintype "passive"))
      (node (ref "J4") (pin "17") (pinfunction "17_17") (pintype "passive"))
      (node (ref "J4") (pin "5") (pinfunction "5_5") (pintype "passive"))
      (node (ref "J7") (pin "9") (pinfunction "9_9") (pintype "passive"))
    )
    (net (code "30") (name "Net-(C12-Pad1)") (class "Default")
      (node (ref "C12") (pin "1") (pinfunction "1_1") (pintype "passive"))
      (node (ref "R8") (pin "1") (pinfunction "1_1") (pintype "passive"))
      (node (ref "R9") (pin "2") (pinfunction "2_2") (pintype "passive"))
    )
    (net (code "31") (name "Net-(C18-Pad1)") (class "Default")
      (node (ref "C18") (pin "1") (pinfunction "1_1") (pintype "passive"))
      (node (ref "R13") (pin "1") (pinfunction "1_1") (pintype "passive"))
      (node (ref "R14") (pin "2") (pinfunction "2_2") (pintype "passive"))
    )
    (net (code "32") (name "Net-(D1-A)") (class "Default")
      (node (ref "D1") (pin "1") (pinfunction "A_1") (pintype "passive"))
      (node (ref "R12") (pin "2") (pinfunction "2_2") (pintype "passive"))
    )
    (net (code "33") (name "Net-(Q1-G)") (class "Default")
      (node (ref "Q1") (pin "1") (pinfunction "G_1") (pintype "passive"))
      (node (ref "R16") (pin "2") (pinfunction "2_2") (pintype "passive"))
      (node (ref "R17") (pin "1") (pinfunction "1_1") (pintype "passive"))
    )
    (net (code "34") (name "Net-(S1-S)") (class "Default")
      (node (ref "R16") (pin "1") (pinfunction "1_1") (pintype "passive"))
      (node (ref "S1") (pin "3") (pinfunction "S_3") (pintype "passive"))
    )
    (net (code "35") (name "Net-(U1-A0)") (class "Default")
      (node (ref "R1") (pin "2") (pinfunction "2_2") (pintype "passive"))
      (node (ref "U1") (pin "7") (pinfunction "A0_7") (pintype "bidirectional"))
    )
    (net (code "36") (name "Net-(U1-A1)") (class "Default")
      (node (ref "R2") (pin "2") (pinfunction "2_2") (pintype "passive"))
      (node (ref "U1") (pin "8") (pinfunction "A1_8") (pintype "bidirectional"))
    )
    (net (code "37") (name "Net-(U2-BOOT)") (class "Default")
      (node (ref "C9") (pin "1") (pinfunction "1_1") (pintype "passive"))
      (node (ref "U2") (pin "6") (pinfunction "BOOT_6") (pintype "bidirectional"))
    )
    (net (code "38") (name "Net-(U2-FB)") (class "Default")
      (node (ref "C12") (pin "2") (pinfunction "2_2") (pintype "passive"))
      (node (ref "R10") (pin "2") (pinfunction "2_2") (pintype "passive"))
      (node (ref "R9") (pin "1") (pinfunction "1_1") (pintype "passive"))
      (node (ref "U2") (pin "4") (pinfunction "FB_4") (pintype "bidirectional"))
    )
    (net (code "39") (name "Net-(U2-SW)") (class "Default")
      (node (ref "C9") (pin "2") (pinfunction "2_2") (pintype "passive"))
      (node (ref "L2") (pin "1") (pinfunction "1_1") (pintype "passive"))
      (node (ref "U2") (pin "2") (pinfunction "SW_2") (pintype "bidirectional"))
    )
    (net (code "40") (name "Net-(U3-BOOT)") (class "Default")
      (node (ref "C15") (pin "1") (pinfunction "1_1") (pintype "passive"))
      (node (ref "U3") (pin "6") (pinfunction "BOOT_6") (pintype "bidirectional"))
    )
    (net (code "41") (name "Net-(U3-FB)") (class "Default")
      (node (ref "C18") (pin "2") (pinfunction "2_2") (pintype "passive"))
      (node (ref "R14") (pin "1") (pinfunction "1_1") (pintype "passive"))
      (node (ref "R15") (pin "2") (pinfunction "2_2") (pintype "passive"))
      (node (ref "U3") (pin "4") (pinfunction "FB_4") (pintype "bidirectional"))
    )
    (net (code "42") (name "Net-(U3-SW)") (class "Default")
      (node (ref "C15") (pin "2") (pinfunction "2_2") (pintype "passive"))
      (node (ref "L3") (pin "1") (pinfunction "1_1") (pintype "passive"))
      (node (ref "U3") (pin "2") (pinfunction "SW_2") (pintype "bidirectional"))
    )
    (net (code "43") (name "SCL") (class "Default")
      (node (ref "D12") (pin "1") (pinfunction "1_1") (pintype "bidirectional"))
      (node (ref "J8") (pin "2") (pinfunction "2_2") (pintype "passive"))
      (node (ref "R6") (pin "1") (pinfunction "1_1") (pintype "passive"))
      (node (ref "U1") (pin "5") (pinfunction "SCL_5") (pintype "bidirectional"))
      (node (ref "X5") (pin "1") (pinfunction "S_1") (pintype "passive"))
    )
    (net (code "44") (name "SDA") (class "Default")
      (node (ref "D13") (pin "1") (pinfunction "1_1") (pintype "bidirectional"))
      (node (ref "J8") (pin "4") (pinfunction "4_4") (pintype "passive"))
      (node (ref "R7") (pin "1") (pinfunction "1_1") (pintype "passive"))
      (node (ref "U1") (pin "6") (pinfunction "SDA_6") (pintype "bidirectional"))
      (node (ref "X5") (pin "2") (pinfunction "S_2") (pintype "passive"))
    )
    (net (code "45") (name "SP1") (class "Default")
      (node (ref "D4") (pin "1") (pinfunction "1_1") (pintype "bidirectional"))
      (node (ref "J4") (pin "18") (pinfunction "18_18") (pintype "passive"))
      (node (ref "J8") (pin "10") (pinfunction "10_10") (pintype "passive"))
    )
    (net (code "46") (name "SP2") (class "Default")
      (node (ref "D36") (pin "1") (pinfunction "1_1") (pintype "bidirectional"))
      (node (ref "J4") (pin "19") (pinfunction "19_19") (pintype "passive"))
      (node (ref "J8") (pin "12") (pinfunction "12_12") (pintype "passive"))
    )
    (net (code "47") (name "SP3") (class "Default")
      (node (ref "D37") (pin "1") (pinfunction "1_1") (pintype "bidirectional"))
      (node (ref "J4") (pin "20") (pinfunction "20_20") (pintype "passive"))
      (node (ref "J8") (pin "14") (pinfunction "14_14") (pintype "passive"))
    )
    (net (code "48") (name "SP4") (class "Default")
      (node (ref "D38") (pin "1") (pinfunction "1_1") (pintype "bidirectional"))
      (node (ref "J4") (pin "21") (pinfunction "21_21") (pintype "passive"))
      (node (ref "J8") (pin "16") (pinfunction "16_16") (pintype "passive"))
    )
    (net (code "49") (name "THER_A_SCL") (class "Default")
      (node (ref "D18") (pin "1") (pinfunction "1_1") (pintype "bidirectional"))
      (node (ref "J4") (pin "2") (pinfunction "2_2") (pintype "passive"))
      (node (ref "J8") (pin "7") (pinfunction "7_7") (pintype "passive"))
    )
    (net (code "50") (name "THER_A_SDA") (class "Default")
      (node (ref "D17") (pin "1") (pinfunction "1_1") (pintype "bidirectional"))
      (node (ref "J4") (pin "1") (pinfunction "1_1") (pintype "passive"))
      (node (ref "J8") (pin "9") (pinfunction "9_9") (pintype "passive"))
    )
    (net (code "51") (name "THER_B_SCL") (class "Default")
      (node (ref "D15") (pin "1") (pinfunction "1_1") (pintype "bidirectional"))
      (node (ref "J4") (pin "4") (pinfunction "4_4") (pintype "passive"))
      (node (ref "J8") (pin "3") (pinfunction "3_3") (pintype "passive"))
    )
    (net (code "52") (name "THER_B_SDA") (class "Default")
      (node (ref "D16") (pin "1") (pinfunction "1_1") (pintype "bidirectional"))
      (node (ref "J4") (pin "3") (pinfunction "3_3") (pintype "passive"))
      (node (ref "J8") (pin "5") (pinfunction "5_5") (pintype "passive"))
    )
    (net (code "53") (name "VIN") (class "Default")
      (node (ref "C13") (pin "1") (pinfunction "1_1") (pintype "passive"))
      (node (ref "C14") (pin "1") (pinfunction "1_1") (pintype "passive"))
      (node (ref "C21") (pin "+") (pinfunction "+_+") (pintype "passive"))
      (node (ref "C7") (pin "1") (pinfunction "1_1") (pintype "passive"))
      (node (ref "C8") (pin "1") (pinfunction "1_1") (pintype "passive"))
      (node (ref "Q1") (pin "4") (pinfunction "D_4") (pintype "passive"))
      (node (ref "U2") (pin "3") (pinfunction "VIN_3") (pintype "bidirectional"))
      (node (ref "U3") (pin "3") (pinfunction "VIN_3") (pintype "bidirectional"))
    )
    (net (code "54") (name "VIN+") (class "Default")
      (node (ref "R5") (pin "2") (pinfunction "2_2") (pintype "passive"))
      (node (ref "U$9") (pin "+") (pinfunction "VCC_+") (pintype "bidirectional"))
      (node (ref "U1") (pin "1") (pinfunction "VIN+_1") (pintype "bidirectional"))
    )
    (net (code "55") (name "VIN-") (class "Default")
      (node (ref "D1") (pin "3") (pinfunction "C_3") (pintype "passive"))
      (node (ref "Q1") (pin "3") (pinfunction "S_3") (pintype "passive"))
      (node (ref "R17") (pin "2") (pinfunction "2_2") (pintype "passive"))
      (node (ref "R5") (pin "1") (pinfunction "1_1") (pintype "passive"))
      (node (ref "U1") (pin "2") (pinfunction "VIN-_2") (pintype "bidirectional"))
    )
    (net (code "56") (name "unconnected-(J1-PadMH1)") (class "Default")
      (node (ref "J1") (pin "MH1") (pinfunction "MH1_MH1") (pintype "passive"))
    )
    (net (code "57") (name "unconnected-(J1-PadMH2)") (class "Default")
      (node (ref "J1") (pin "MH2") (pinfunction "MH2_MH2") (pintype "passive"))
    )
    (net (code "58") (name "unconnected-(J4-Pad22)") (class "Default")
      (node (ref "J4") (pin "22") (pinfunction "22_22") (pintype "passive"))
    )
    (net (code "59") (name "unconnected-(J4-Pad23)") (class "Default")
      (node (ref "J4") (pin "23") (pinfunction "23_23") (pintype "passive"))
    )
    (net (code "60") (name "unconnected-(J4-Pad24)") (class "Default")
      (node (ref "J4") (pin "24") (pinfunction "24_24") (pintype "passive"))
    )
    (net (code "61") (name "unconnected-(J4-Pad25)") (class "Default")
      (node (ref "J4") (pin "25") (pinfunction "25_25") (pintype "passive"))
    )
    (net (code "62") (name "unconnected-(J5-Pad2)") (class "Default")
      (node (ref "J5") (pin "2") (pinfunction "2_2") (pintype "passive"))
    )
    (net (code "63") (name "unconnected-(J5-Pad4)") (class "Default")
      (node (ref "J5") (pin "4") (pinfunction "4_4") (pintype "passive"))
    )
    (net (code "64") (name "unconnected-(J5-Pad6)") (class "Default")
      (node (ref "J5") (pin "6") (pinfunction "6_6") (pintype "passive"))
    )
    (net (code "65") (name "unconnected-(J5-Pad8)") (class "Default")
      (node (ref "J5") (pin "8") (pinfunction "8_8") (pintype "passive"))
    )
    (net (code "66") (name "unconnected-(J5-Pad10)") (class "Default")
      (node (ref "J5") (pin "10") (pinfunction "10_10") (pintype "passive"))
    )
    (net (code "67") (name "unconnected-(J5-Pad12)") (class "Default")
      (node (ref "J5") (pin "12") (pinfunction "12_12") (pintype "passive"))
    )
    (net (code "68") (name "unconnected-(J5-Pad14)") (class "Default")
      (node (ref "J5") (pin "14") (pinfunction "14_14") (pintype "passive"))
    )
    (net (code "69") (name "unconnected-(J5-Pad16)") (class "Default")
      (node (ref "J5") (pin "16") (pinfunction "16_16") (pintype "passive"))
    )
    (net (code "70") (name "unconnected-(J6-Pad2)") (class "Default")
      (node (ref "J6") (pin "2") (pinfunction "2_2") (pintype "passive"))
    )
    (net (code "71") (name "unconnected-(J6-Pad4)") (class "Default")
      (node (ref "J6") (pin "4") (pinfunction "4_4") (pintype "passive"))
    )
    (net (code "72") (name "unconnected-(J6-Pad5)") (class "Default")
      (node (ref "J6") (pin "5") (pinfunction "5_5") (pintype "passive"))
    )
    (net (code "73") (name "unconnected-(J6-Pad6)") (class "Default")
      (node (ref "J6") (pin "6") (pinfunction "6_6") (pintype "passive"))
    )
    (net (code "74") (name "unconnected-(J6-Pad7)") (class "Default")
      (node (ref "J6") (pin "7") (pinfunction "7_7") (pintype "passive"))
    )
    (net (code "75") (name "unconnected-(J6-Pad8)") (class "Default")
      (node (ref "J6") (pin "8") (pinfunction "8_8") (pintype "passive"))
    )
    (net (code "76") (name "unconnected-(J6-Pad10)") (class "Default")
      (node (ref "J6") (pin "10") (pinfunction "10_10") (pintype "passive"))
    )
    (net (code "77") (name "unconnected-(J6-Pad12)") (class "Default")
      (node (ref "J6") (pin "12") (pinfunction "12_12") (pintype "passive"))
    )
    (net (code "78") (name "unconnected-(J6-Pad14)") (class "Default")
      (node (ref "J6") (pin "14") (pinfunction "14_14") (pintype "passive"))
    )
    (net (code "79") (name "unconnected-(J6-Pad16)") (class "Default")
      (node (ref "J6") (pin "16") (pinfunction "16_16") (pintype "passive"))
    )
    (net (code "80") (name "unconnected-(J7-Pad11)") (class "Default")
      (node (ref "J7") (pin "11") (pinfunction "11_11") (pintype "passive"))
    )
    (net (code "81") (name "unconnected-(J8-Pad6)") (class "Default")
      (node (ref "J8") (pin "6") (pinfunction "6_6") (pintype "passive"))
    )
    (net (code "82") (name "unconnected-(J8-Pad8)") (class "Default")
      (node (ref "J8") (pin "8") (pinfunction "8_8") (pintype "passive"))
    )
    (net (code "83") (name "unconnected-(PAD1-P-Pad1)") (class "Default")
      (node (ref "PAD1") (pin "1") (pinfunction "P_1") (pintype "passive"))
    )
    (net (code "84") (name "unconnected-(PAD2-P-Pad1)") (class "Default")
      (node (ref "PAD2") (pin "1") (pinfunction "P_1") (pintype "passive"))
    )
    (net (code "85") (name "unconnected-(PAD3-P-Pad1)") (class "Default")
      (node (ref "PAD3") (pin "1") (pinfunction "P_1") (pintype "passive"))
    )
    (net (code "86") (name "unconnected-(PAD4-P-Pad1)") (class "Default")
      (node (ref "PAD4") (pin "1") (pinfunction "P_1") (pintype "passive"))
    )
    (net (code "87") (name "unconnected-(PAD5-P-Pad1)") (class "Default")
      (node (ref "PAD5") (pin "1") (pinfunction "P_1") (pintype "passive"))
    )
    (net (code "88") (name "unconnected-(PAD6-P-Pad1)") (class "Default")
      (node (ref "PAD6") (pin "1") (pinfunction "P_1") (pintype "passive"))
    )
    (net (code "89") (name "unconnected-(PAD7-P-Pad1)") (class "Default")
      (node (ref "PAD7") (pin "1") (pinfunction "P_1") (pintype "passive"))
    )
    (net (code "90") (name "unconnected-(PAD8-P-Pad1)") (class "Default")
      (node (ref "PAD8") (pin "1") (pinfunction "P_1") (pintype "passive"))
    )
    (net (code "91") (name "unconnected-(PAD9-P-Pad1)") (class "Default")
      (node (ref "PAD9") (pin "1") (pinfunction "P_1") (pintype "passive"))
    )
    (net (code "92") (name "unconnected-(PAD10-P-Pad1)") (class "Default")
      (node (ref "PAD10") (pin "1") (pinfunction "P_1") (pintype "passive"))
    )
    (net (code "93") (name "unconnected-(PAD11-P-Pad1)") (class "Default")
      (node (ref "PAD11") (pin "1") (pinfunction "P_1") (pintype "passive"))
    )
    (net (code "94") (name "unconnected-(PAD12-P-Pad1)") (class "Default")
      (node (ref "PAD12") (pin "1") (pinfunction "P_1") (pintype "passive"))
    )
    (net (code "95") (name "unconnected-(PAD13-P-Pad1)") (class "Default")
      (node (ref "PAD13") (pin "1") (pinfunction "P_1") (pintype "passive"))
    )
    (net (code "96") (name "unconnected-(PAD14-P-Pad1)") (class "Default")
      (node (ref "PAD14") (pin "1") (pinfunction "P_1") (pintype "passive"))
    )
    (net (code "97") (name "unconnected-(PAD15-P-Pad1)") (class "Default")
      (node (ref "PAD15") (pin "1") (pinfunction "P_1") (pintype "passive"))
    )
    (net (code "98") (name "unconnected-(PAD16-P-Pad1)") (class "Default")
      (node (ref "PAD16") (pin "1") (pinfunction "P_1") (pintype "passive"))
    )
    (net (code "99") (name "unconnected-(PAD17-P-Pad1)") (class "Default")
      (node (ref "PAD17") (pin "1") (pinfunction "P_1") (pintype "passive"))
    )
    (net (code "100") (name "unconnected-(PAD18-P-Pad1)") (class "Default")
      (node (ref "PAD18") (pin "1") (pinfunction "P_1") (pintype "passive"))
    )
    (net (code "101") (name "unconnected-(PAD19-P-Pad1)") (class "Default")
      (node (ref "PAD19") (pin "1") (pinfunction "P_1") (pintype "passive"))
    )
    (net (code "102") (name "unconnected-(PAD20-P-Pad1)") (class "Default")
      (node (ref "PAD20") (pin "1") (pinfunction "P_1") (pintype "passive"))
    )
    (net (code "103") (name "unconnected-(PAD21-P-Pad1)") (class "Default")
      (node (ref "PAD21") (pin "1") (pinfunction "P_1") (pintype "passive"))
    )
    (net (code "104") (name "unconnected-(PAD22-P-Pad1)") (class "Default")
      (node (ref "PAD22") (pin "1") (pinfunction "P_1") (pintype "passive"))
    )
    (net (code "105") (name "unconnected-(PAD23-P-Pad1)") (class "Default")
      (node (ref "PAD23") (pin "1") (pinfunction "P_1") (pintype "passive"))
    )
    (net (code "106") (name "unconnected-(PAD24-P-Pad1)") (class "Default")
      (node (ref "PAD24") (pin "1") (pinfunction "P_1") (pintype "passive"))
    )
    (net (code "107") (name "unconnected-(PAD25-P-Pad1)") (class "Default")
      (node (ref "PAD25") (pin "1") (pinfunction "P_1") (pintype "passive"))
    )
    (net (code "108") (name "unconnected-(PAD26-P-Pad1)") (class "Default")
      (node (ref "PAD26") (pin "1") (pinfunction "P_1") (pintype "passive"))
    )
    (net (code "109") (name "unconnected-(PAD27-P-Pad1)") (class "Default")
      (node (ref "PAD27") (pin "1") (pinfunction "P_1") (pintype "passive"))
    )
    (net (code "110") (name "unconnected-(PAD28-P-Pad1)") (class "Default")
      (node (ref "PAD28") (pin "1") (pinfunction "P_1") (pintype "passive"))
    )
    (net (code "111") (name "unconnected-(PAD29-P-Pad1)") (class "Default")
      (node (ref "PAD29") (pin "1") (pinfunction "P_1") (pintype "passive"))
    )
    (net (code "112") (name "unconnected-(PAD30-P-Pad1)") (class "Default")
      (node (ref "PAD30") (pin "1") (pinfunction "P_1") (pintype "passive"))
    )
    (net (code "113") (name "unconnected-(PAD31-P-Pad1)") (class "Default")
      (node (ref "PAD31") (pin "1") (pinfunction "P_1") (pintype "passive"))
    )
    (net (code "114") (name "unconnected-(PAD32-P-Pad1)") (class "Default")
      (node (ref "PAD32") (pin "1") (pinfunction "P_1") (pintype "passive"))
    )
    (net (code "115") (name "unconnected-(PAD33-P-Pad1)") (class "Default")
      (node (ref "PAD33") (pin "1") (pinfunction "P_1") (pintype "passive"))
    )
    (net (code "116") (name "unconnected-(PAD34-P-Pad1)") (class "Default")
      (node (ref "PAD34") (pin "1") (pinfunction "P_1") (pintype "passive"))
    )
    (net (code "117") (name "unconnected-(PAD35-P-Pad1)") (class "Default")
      (node (ref "PAD35") (pin "1") (pinfunction "P_1") (pintype "passive"))
    )
    (net (code "118") (name "unconnected-(PAD36-P-Pad1)") (class "Default")
      (node (ref "PAD36") (pin "1") (pinfunction "P_1") (pintype "passive"))
    )
    (net (code "119") (name "unconnected-(PAD37-P-Pad1)") (class "Default")
      (node (ref "PAD37") (pin "1") (pinfunction "P_1") (pintype "passive"))
    )
    (net (code "120") (name "unconnected-(PAD38-P-Pad1)") (class "Default")
      (node (ref "PAD38") (pin "1") (pinfunction "P_1") (pintype "passive"))
    )
    (net (code "121") (name "unconnected-(PAD39-P-Pad1)") (class "Default")
      (node (ref "PAD39") (pin "1") (pinfunction "P_1") (pintype "passive"))
    )
    (net (code "122") (name "unconnected-(PAD41-P-Pad1)") (class "Default")
      (node (ref "PAD41") (pin "1") (pinfunction "P_1") (pintype "passive"))
    )
    (net (code "123") (name "unconnected-(PAD43-P-Pad1)") (class "Default")
      (node (ref "PAD43") (pin "1") (pinfunction "P_1") (pintype "passive"))
    )
    (net (code "124") (name "unconnected-(PAD45-P-Pad1)") (class "Default")
      (node (ref "PAD45") (pin "1") (pinfunction "P_1") (pintype "passive"))
    )
    (net (code "125") (name "unconnected-(S1-O-Pad1)") (class "Default")
      (node (ref "S1") (pin "1") (pinfunction "O_1") (pintype "passive"))
    )
  )
)
